# COEXPIX_schematics.net
KiCad netlist of a schematic drawn in Altium Designer
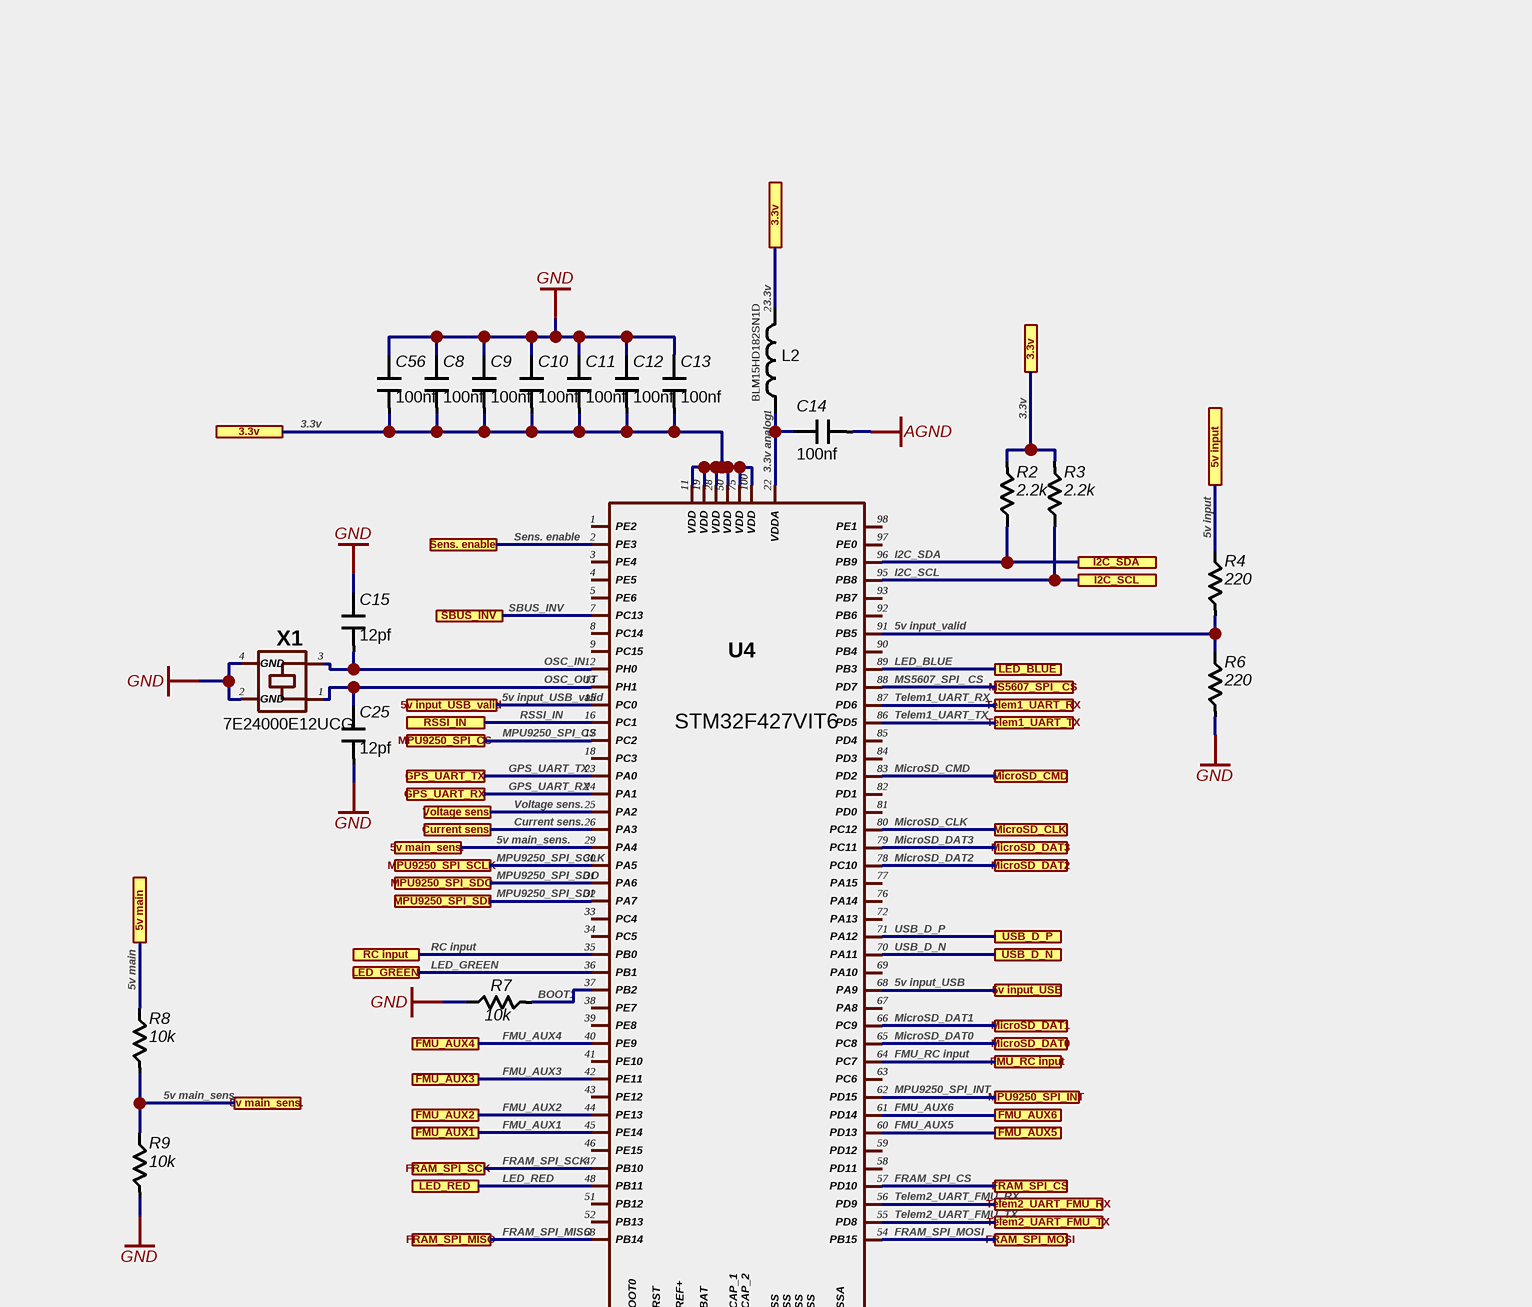
[diagram p0: COEXPIX schematics.SchDoc, top left]
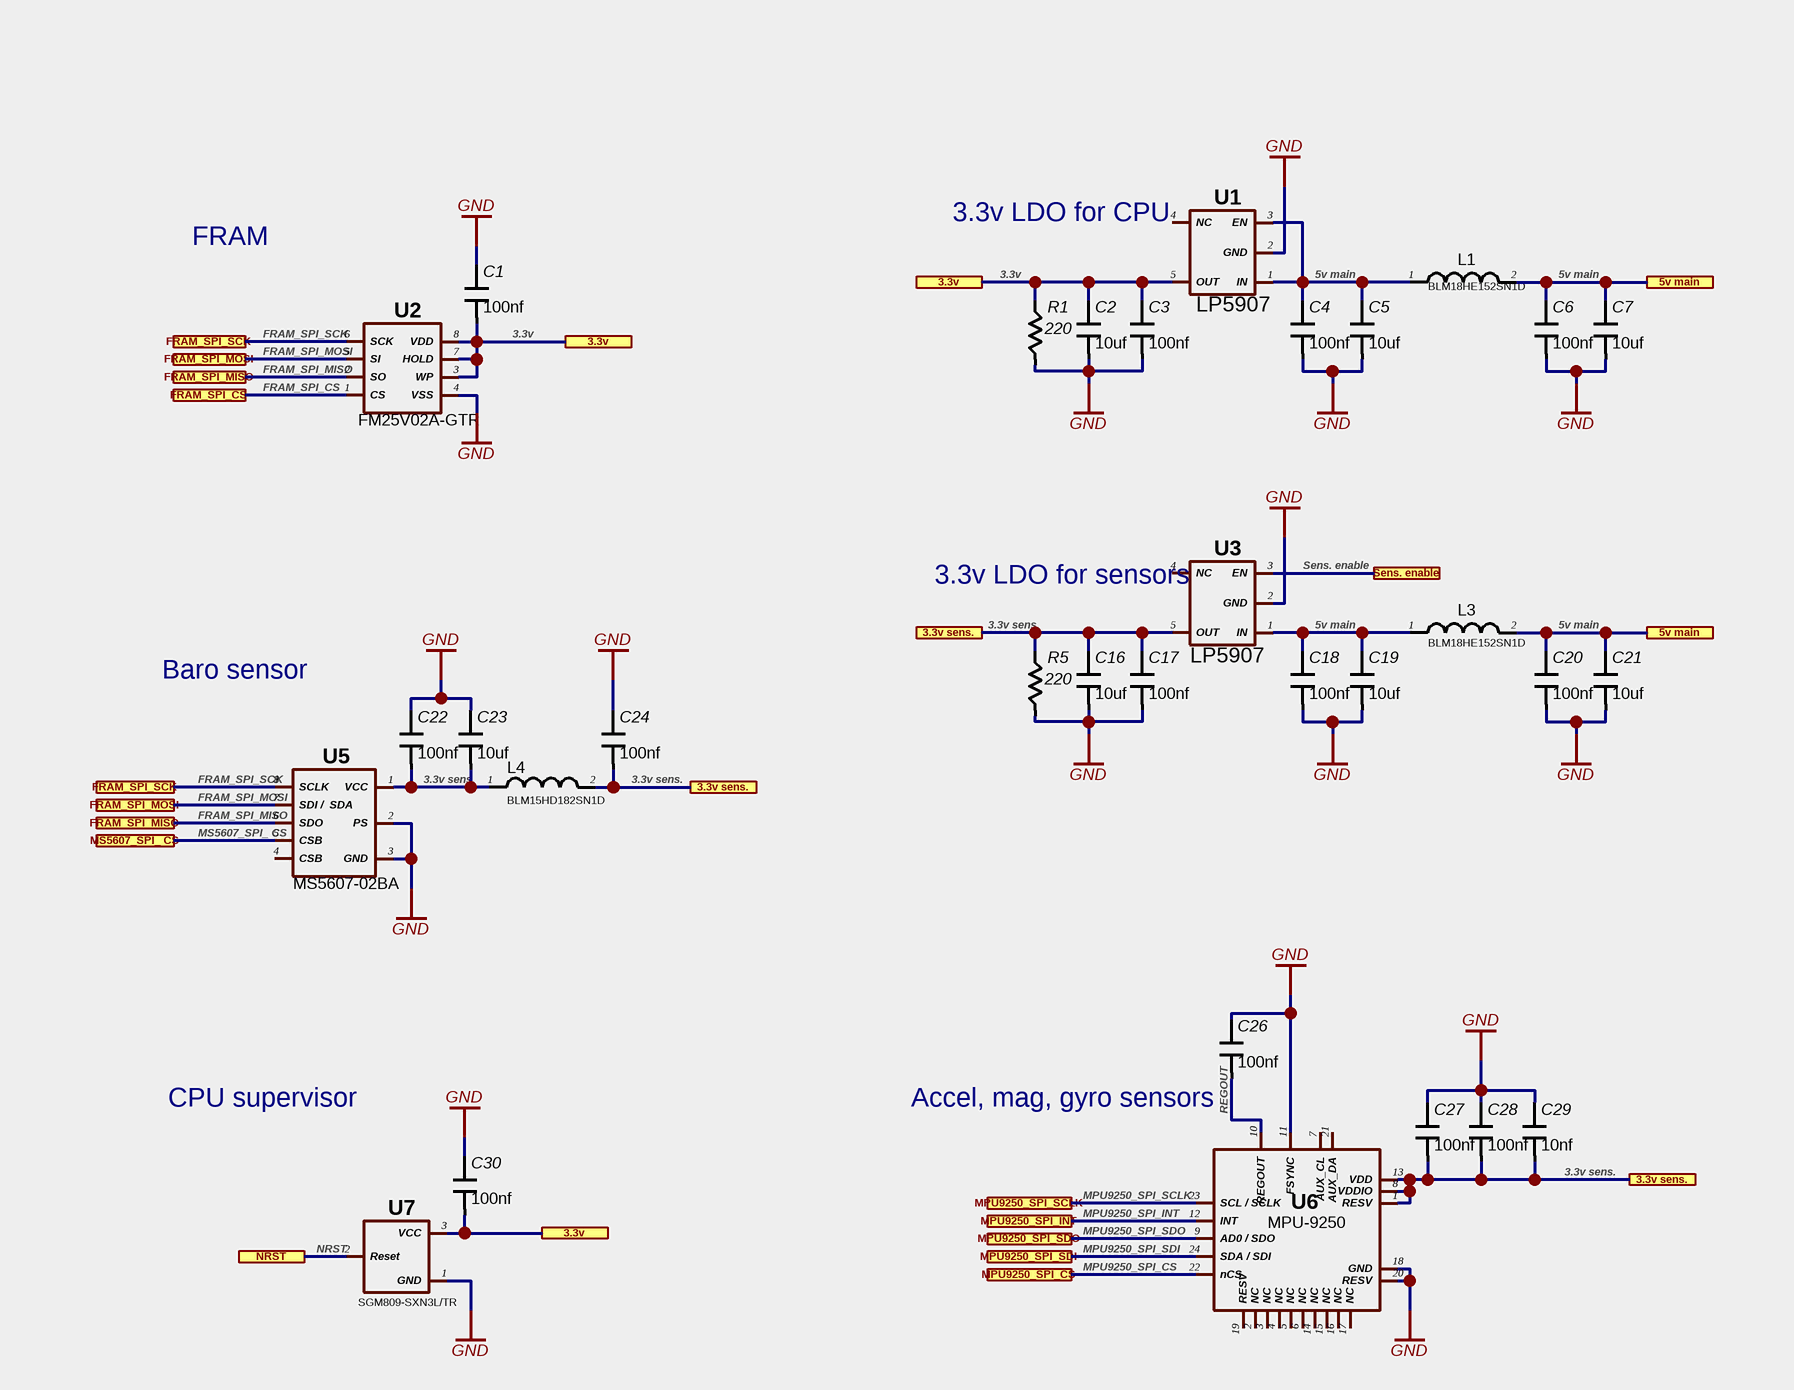
[diagram p1: COEXPIX schematics.SchDoc, top right]
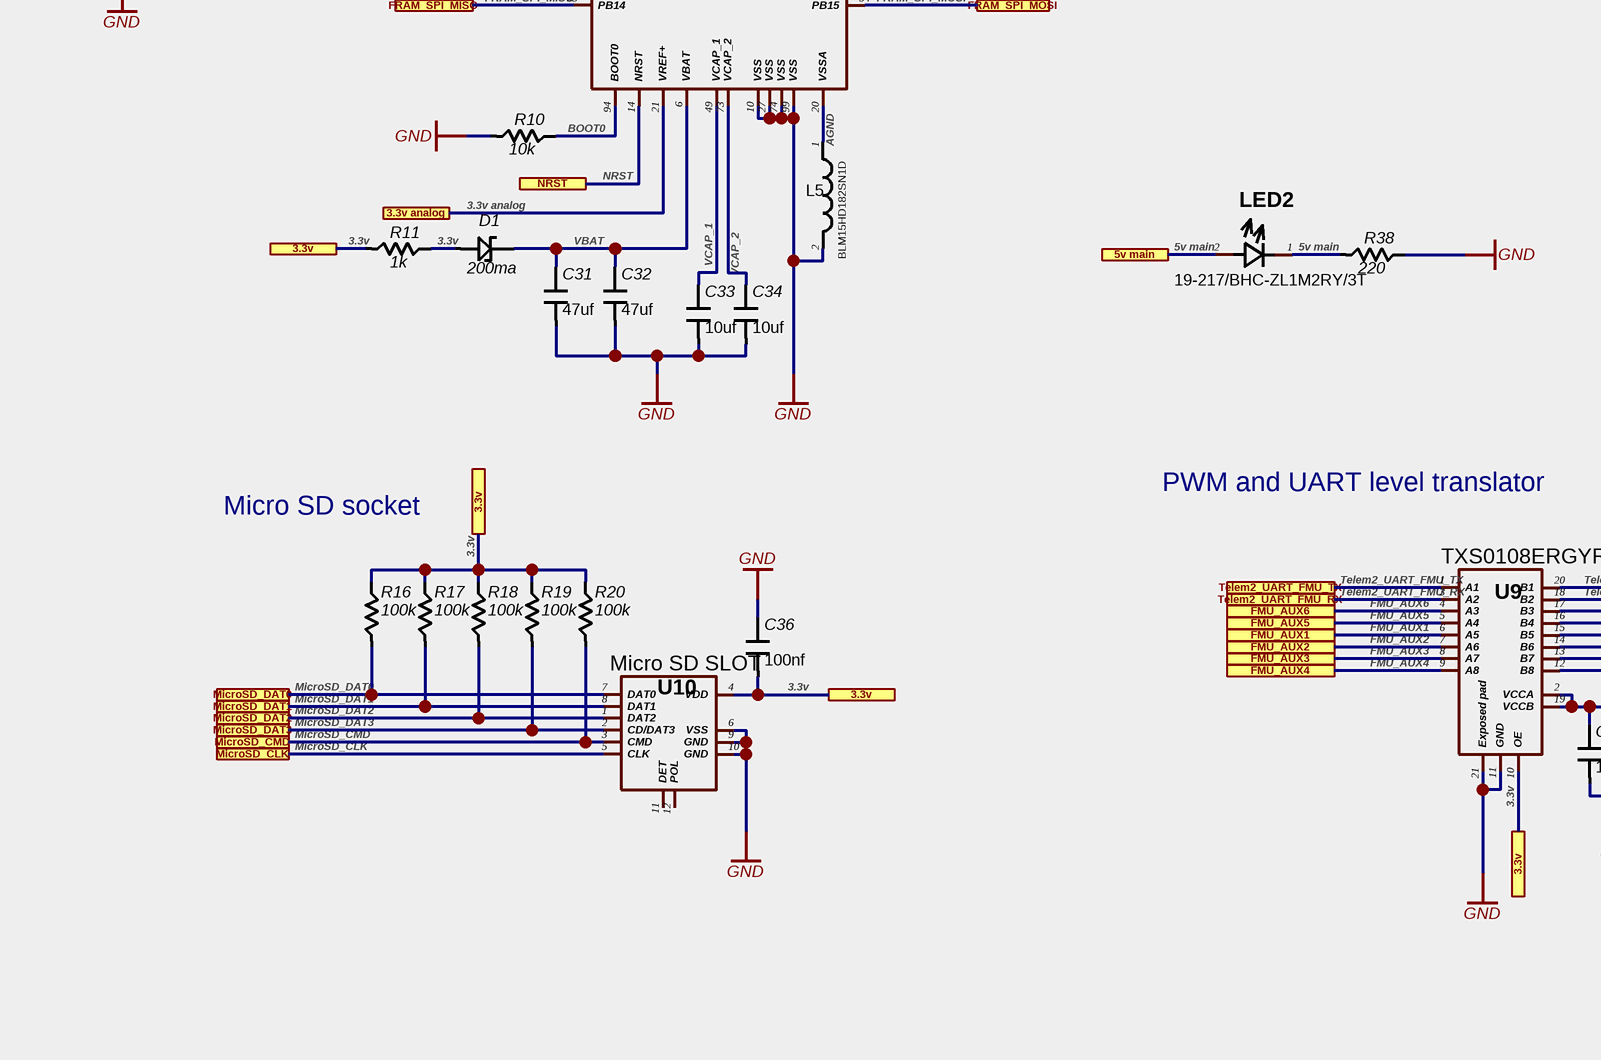
[diagram p2: COEXPIX schematics.SchDoc, bottom left]
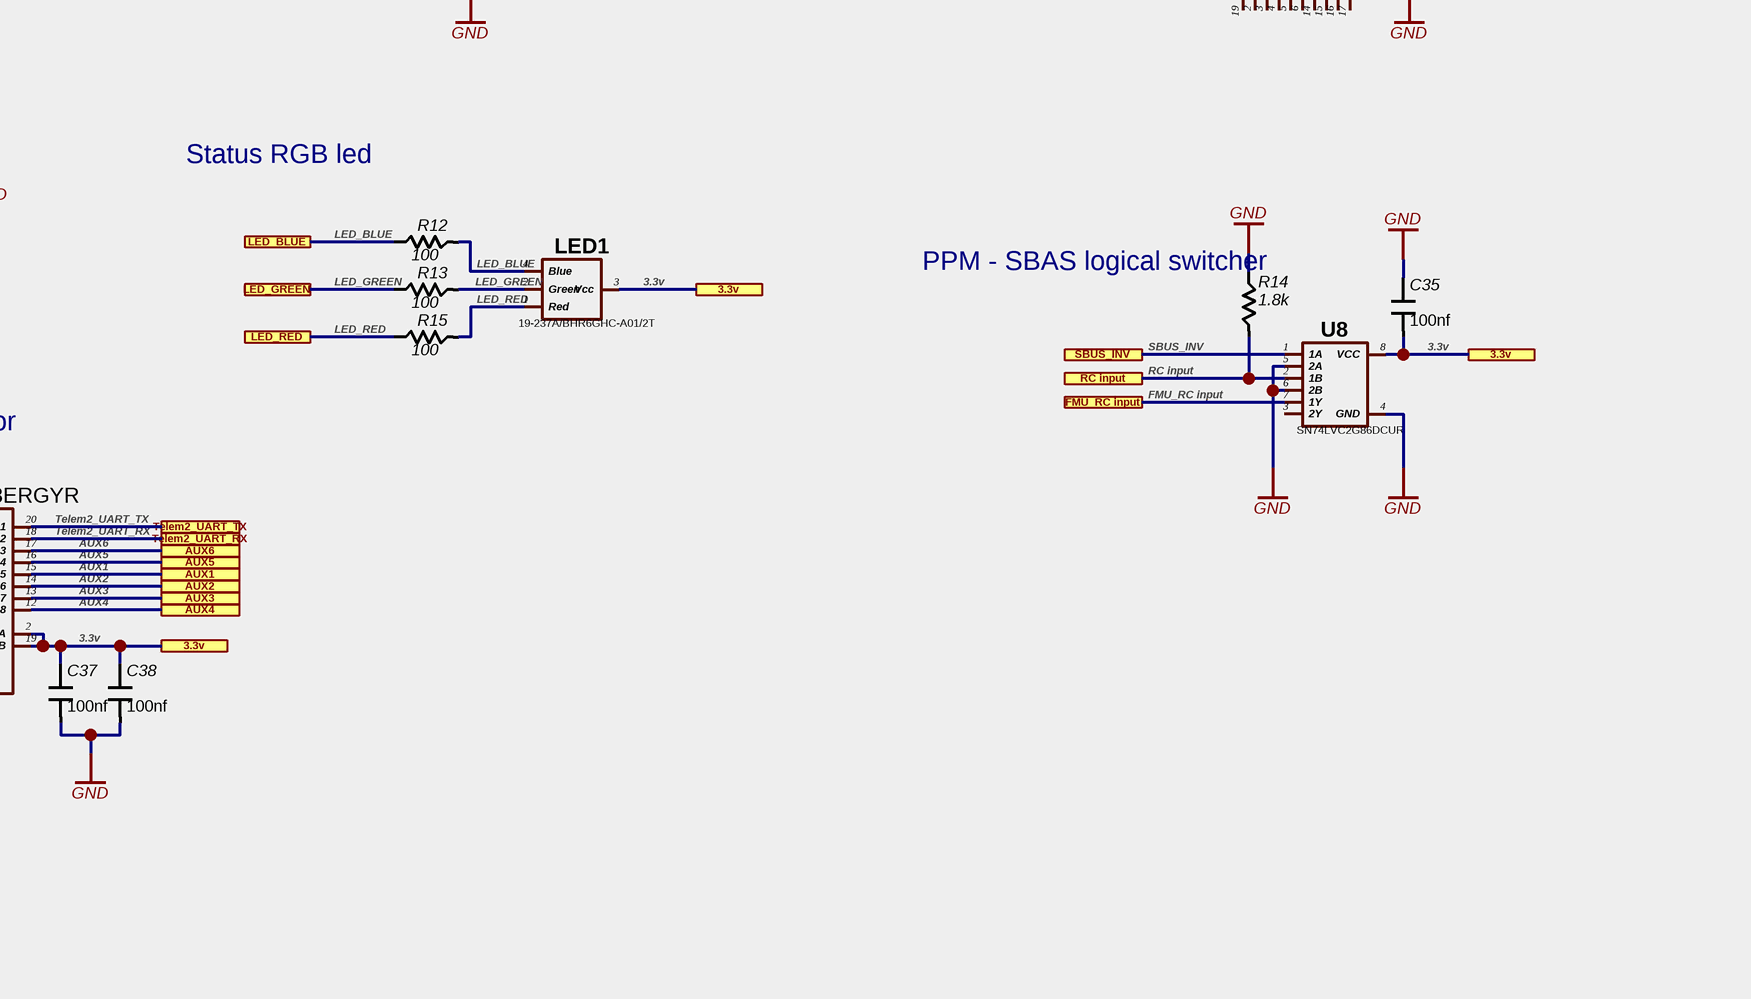
[diagram p3: COEXPIX schematics.SchDoc, bottom right]

(export (version "E")
  (design (tool "Eeschema 10.0.6"))
  (components
    (comp (ref "C1")
      (value "100nf")
      (footprint "Capasitor 0402")
      (description "Multilayer Ceramic Capacitors MLCC - SMD/SMT 100nF 16V 0402")
      (fields (field (name "PART NUMBER") "CC0402KRX7R7BB104") (field (name "MANUFACTURER") "YAGEO"))
      (libsource (lib "Schematic symbols library") (part "Capacitor MLCC"))
    )
    (comp (ref "C2")
      (value "10uf")
      (footprint "Capasitor 0402")
      (description "Multilayer Ceramic Capacitors MLCC - SMD/SMT 10uF 6.3V 0402")
      (fields (field (name "PART NUMBER") "JMK105CBJ106MV-F") (field (name "MANUFACTURER") "Taiyo Yuden"))
      (libsource (lib "Schematic symbols library") (part "Capacitor MLCC"))
    )
    (comp (ref "C3")
      (value "100nf")
      (footprint "Capasitor 0402")
      (description "Multilayer Ceramic Capacitors MLCC - SMD/SMT 100nF 16V 0402")
      (fields (field (name "PART NUMBER") "CC0402KRX7R7BB104") (field (name "MANUFACTURER") "YAGEO"))
      (libsource (lib "Schematic symbols library") (part "Capacitor MLCC"))
    )
    (comp (ref "C4")
      (value "100nf")
      (footprint "Capasitor 0402")
      (description "Multilayer Ceramic Capacitors MLCC - SMD/SMT 100nF 16V 0402")
      (fields (field (name "PART NUMBER") "CC0402KRX7R7BB104") (field (name "MANUFACTURER") "YAGEO"))
      (libsource (lib "Schematic symbols library") (part "Capacitor MLCC"))
    )
    (comp (ref "C5")
      (value "10uf")
      (footprint "Capasitor 0402")
      (description "Multilayer Ceramic Capacitors MLCC - SMD/SMT 10uF 6.3V 0402")
      (fields (field (name "PART NUMBER") "JMK105CBJ106MV-F") (field (name "MANUFACTURER") "Taiyo Yuden"))
      (libsource (lib "") (part "Capacitor MLCC_1"))
    )
    (comp (ref "C6")
      (value "100nf")
      (footprint "Capasitor 0402")
      (description "Multilayer Ceramic Capacitors MLCC - SMD/SMT 100nF 16V 0402")
      (fields (field (name "PART NUMBER") "CC0402KRX7R7BB104") (field (name "MANUFACTURER") "YAGEO"))
      (libsource (lib "Schematic symbols library") (part "Capacitor MLCC"))
    )
    (comp (ref "C7")
      (value "10uf")
      (footprint "Capasitor 0402")
      (description "X5R 6.3v 10uf")
      (fields (field (name "PART NUMBER") "JMK105CBJ106MV-F") (field (name "MANUFACTURER") "Taiyo Yuden"))
      (libsource (lib "Schematic symbols library") (part "Capacitor MLCC"))
    )
    (comp (ref "C8")
      (value "100nf")
      (footprint "Capasitor 0402")
      (description "Multilayer Ceramic Capacitors MLCC - SMD/SMT 100nF 16V 0402")
      (fields (field (name "PART NUMBER") "CC0402KRX7R7BB104") (field (name "MANUFACTURER") "YAGEO"))
      (libsource (lib "Schematic symbols library") (part "Capacitor MLCC"))
    )
    (comp (ref "C9")
      (value "100nf")
      (footprint "Capasitor 0402")
      (description "Multilayer Ceramic Capacitors MLCC - SMD/SMT 100nF 16V 0402")
      (fields (field (name "PART NUMBER") "CC0402KRX7R7BB104") (field (name "MANUFACTURER") "YAGEO"))
      (libsource (lib "Schematic symbols library") (part "Capacitor MLCC"))
    )
    (comp (ref "C10")
      (value "100nf")
      (footprint "Capasitor 0402")
      (description "Multilayer Ceramic Capacitors MLCC - SMD/SMT 100nF 16V 0402")
      (fields (field (name "PART NUMBER") "CC0402KRX7R7BB104") (field (name "MANUFACTURER") "YAGEO"))
      (libsource (lib "Schematic symbols library") (part "Capacitor MLCC"))
    )
    (comp (ref "C11")
      (value "100nf")
      (footprint "Capasitor 0402")
      (description "Multilayer Ceramic Capacitors MLCC - SMD/SMT 100nF 16V 0402")
      (fields (field (name "PART NUMBER") "CC0402KRX7R7BB104") (field (name "MANUFACTURER") "YAGEO"))
      (libsource (lib "Schematic symbols library") (part "Capacitor MLCC"))
    )
    (comp (ref "C12")
      (value "100nf")
      (footprint "Capasitor 0402")
      (description "Multilayer Ceramic Capacitors MLCC - SMD/SMT 100nF 16V 0402")
      (fields (field (name "PART NUMBER") "CC0402KRX7R7BB104") (field (name "MANUFACTURER") "YAGEO"))
      (libsource (lib "Schematic symbols library") (part "Capacitor MLCC"))
    )
    (comp (ref "C13")
      (value "100nf")
      (footprint "Capasitor 0402")
      (description "Multilayer Ceramic Capacitors MLCC - SMD/SMT 100nF 16V 0402")
      (fields (field (name "PART NUMBER") "CC0402KRX7R7BB104") (field (name "MANUFACTURER") "YAGEO"))
      (libsource (lib "Schematic symbols library") (part "Capacitor MLCC"))
    )
    (comp (ref "C14")
      (value "100nf")
      (footprint "Capasitor 0402")
      (description "Multilayer Ceramic Capacitors MLCC - SMD/SMT 100nF 16V 0402")
      (fields (field (name "PART NUMBER") "CC0402KRX7R7BB104") (field (name "MANUFACTURER") "YAGEO"))
      (libsource (lib "Schematic symbols library") (part "Capacitor MLCC"))
    )
    (comp (ref "C15")
      (value "12pf")
      (footprint "Capasitor 0402")
      (description "Multilayer Ceramic Capacitors MLCC - SMD/SMT 12pF 50V 0402")
      (fields (field (name "PART NUMBER") "CC0402JRNPO9BN120") (field (name "MANUFACTURER") "YAGEO"))
      (libsource (lib "Schematic symbols library") (part "Capacitor MLCC"))
    )
    (comp (ref "C16")
      (value "10uf")
      (footprint "Capasitor 0402")
      (description "Multilayer Ceramic Capacitors MLCC - SMD/SMT 10uF 6.3V 0402")
      (fields (field (name "PART NUMBER") "JMK105CBJ106MV-F") (field (name "MANUFACTURER") "Taiyo Yuden"))
      (libsource (lib "Schematic symbols library") (part "Capacitor MLCC"))
    )
    (comp (ref "C17")
      (value "100nf")
      (footprint "Capasitor 0402")
      (description "Multilayer Ceramic Capacitors MLCC - SMD/SMT 100nF 16V 0402")
      (fields (field (name "PART NUMBER") "CC0402KRX7R7BB104") (field (name "MANUFACTURER") "YAGEO"))
      (libsource (lib "Schematic symbols library") (part "Capacitor MLCC"))
    )
    (comp (ref "C18")
      (value "100nf")
      (footprint "Capasitor 0402")
      (description "Multilayer Ceramic Capacitors MLCC - SMD/SMT 100nF 16V 0402")
      (fields (field (name "PART NUMBER") "CC0402KRX7R7BB104") (field (name "MANUFACTURER") "YAGEO"))
      (libsource (lib "Schematic symbols library") (part "Capacitor MLCC"))
    )
    (comp (ref "C19")
      (value "10uf")
      (footprint "Capasitor 0402")
      (description "Multilayer Ceramic Capacitors MLCC - SMD/SMT 10uF 6.3V 0402")
      (fields (field (name "PART NUMBER") "JMK105CBJ106MV-F") (field (name "MANUFACTURER") "Taiyo Yuden"))
      (libsource (lib "") (part "Capacitor MLCC_1"))
    )
    (comp (ref "C20")
      (value "100nf")
      (footprint "Capasitor 0402")
      (description "Multilayer Ceramic Capacitors MLCC - SMD/SMT 100nF 16V 0402")
      (fields (field (name "PART NUMBER") "CC0402KRX7R7BB104") (field (name "MANUFACTURER") "YAGEO"))
      (libsource (lib "Schematic symbols library") (part "Capacitor MLCC"))
    )
    (comp (ref "C21")
      (value "10uf")
      (footprint "Capasitor 0402")
      (description "X5R 6.3v 10uf")
      (fields (field (name "PART NUMBER") "JMK105CBJ106MV-F") (field (name "MANUFACTURER") "Taiyo Yuden"))
      (libsource (lib "Schematic symbols library") (part "Capacitor MLCC"))
    )
    (comp (ref "C22")
      (value "100nf")
      (footprint "Capasitor 0402")
      (description "Multilayer Ceramic Capacitors MLCC - SMD/SMT 100nF 16V 0402")
      (fields (field (name "PART NUMBER") "CC0402KRX7R7BB104") (field (name "MANUFACTURER") "YAGEO"))
      (libsource (lib "Schematic symbols library") (part "Capacitor MLCC"))
    )
    (comp (ref "C23")
      (value "10uf")
      (footprint "Capasitor 0402")
      (description "X5R 6.3v 10uf")
      (fields (field (name "PART NUMBER") "JMK105CBJ106MV-F") (field (name "MANUFACTURER") "Taiyo Yuden"))
      (libsource (lib "Schematic symbols library") (part "Capacitor MLCC"))
    )
    (comp (ref "C24")
      (value "100nf")
      (footprint "Capasitor 0402")
      (description "Multilayer Ceramic Capacitors MLCC - SMD/SMT 100nF 16V 0402")
      (fields (field (name "PART NUMBER") "CC0402KRX7R7BB104") (field (name "MANUFACTURER") "YAGEO"))
      (libsource (lib "Schematic symbols library") (part "Capacitor MLCC"))
    )
    (comp (ref "C25")
      (value "12pf")
      (footprint "Capasitor 0402")
      (description "Multilayer Ceramic Capacitors MLCC - SMD/SMT 12pF 50V 0402")
      (fields (field (name "PART NUMBER") "CC0402JRNPO9BN120") (field (name "MANUFACTURER") "YAGEO"))
      (libsource (lib "Schematic symbols library") (part "Capacitor MLCC"))
    )
    (comp (ref "C26")
      (value "100nf")
      (footprint "Capasitor 0402")
      (description "Multilayer Ceramic Capacitors MLCC - SMD/SMT 100nF 16V 0402")
      (fields (field (name "PART NUMBER") "CC0402KRX7R7BB104") (field (name "MANUFACTURER") "YAGEO"))
      (libsource (lib "Schematic symbols library") (part "Capacitor MLCC"))
    )
    (comp (ref "C27")
      (value "100nf")
      (footprint "Capasitor 0402")
      (description "Multilayer Ceramic Capacitors MLCC - SMD/SMT 100nF 16V 0402")
      (fields (field (name "PART NUMBER") "CC0402KRX7R7BB104") (field (name "MANUFACTURER") "YAGEO"))
      (libsource (lib "Schematic symbols library") (part "Capacitor MLCC"))
    )
    (comp (ref "C28")
      (value "100nf")
      (footprint "Capasitor 0402")
      (description "Multilayer Ceramic Capacitors MLCC - SMD/SMT 100nF 16V 0402")
      (fields (field (name "PART NUMBER") "CC0402KRX7R7BB104") (field (name "MANUFACTURER") "YAGEO"))
      (libsource (lib "Schematic symbols library") (part "Capacitor MLCC"))
    )
    (comp (ref "C29")
      (value "10nf")
      (footprint "Capasitor 0402")
      (description "Multilayer Ceramic Capacitors MLCC - SMD/SMT 10nF 50V 0402")
      (fields (field (name "PART NUMBER") "CC0402KRX7R9BB103") (field (name "MANUFACTURER") "YAGEO"))
      (libsource (lib "Schematic symbols library") (part "Capacitor MLCC"))
    )
    (comp (ref "C30")
      (value "100nf")
      (footprint "Capasitor 0402")
      (description "Multilayer Ceramic Capacitors MLCC - SMD/SMT 100nF 16V 0402")
      (fields (field (name "PART NUMBER") "CC0402KRX7R7BB104") (field (name "MANUFACTURER") "YAGEO"))
      (libsource (lib "Schematic symbols library") (part "Capacitor MLCC"))
    )
    (comp (ref "C31")
      (value "47uf")
      (footprint "Capasitor 0603")
      (description "Multilayer Ceramic Capacitors MLCC - SMD/SMT 47uF 6.3V 0603")
      (fields (field (name "PART NUMBER") "GRM188R60J476ME15D") (field (name "MANUFACTURER") "Murata"))
      (libsource (lib "Schematic symbols library") (part "Capacitor MLCC"))
    )
    (comp (ref "C32")
      (value "47uf")
      (footprint "Capasitor 0603")
      (description "Multilayer Ceramic Capacitors MLCC - SMD/SMT 47uF 6.3V 0603")
      (fields (field (name "PART NUMBER") "GRM188R60J476ME15D") (field (name "MANUFACTURER") "Murata"))
      (libsource (lib "Schematic symbols library") (part "Capacitor MLCC"))
    )
    (comp (ref "C33")
      (value "10uf")
      (footprint "Capasitor 0402")
      (description "Multilayer Ceramic Capacitors MLCC - SMD/SMT 10uF 6.3V 0402")
      (fields (field (name "PART NUMBER") "JMK105CBJ106MV-F") (field (name "MANUFACTURER") "Taiyo Yuden"))
      (libsource (lib "Schematic symbols library") (part "Capacitor MLCC"))
    )
    (comp (ref "C34")
      (value "10uf")
      (footprint "Capasitor 0402")
      (description "Multilayer Ceramic Capacitors MLCC - SMD/SMT 10uF 6.3V 0402")
      (fields (field (name "PART NUMBER") "JMK105CBJ106MV-F") (field (name "MANUFACTURER") "Taiyo Yuden"))
      (libsource (lib "Schematic symbols library") (part "Capacitor MLCC"))
    )
    (comp (ref "C35")
      (value "100nf")
      (footprint "Capasitor 0402")
      (description "Multilayer Ceramic Capacitors MLCC - SMD/SMT 100nF 16V 0402")
      (fields (field (name "PART NUMBER") "CC0402KRX7R7BB104") (field (name "MANUFACTURER") "YAGEO"))
      (libsource (lib "Schematic symbols library") (part "Capacitor MLCC"))
    )
    (comp (ref "C36")
      (value "100nf")
      (footprint "Capasitor 0402")
      (description "Multilayer Ceramic Capacitors MLCC - SMD/SMT 100nF 16V 0402")
      (fields (field (name "PART NUMBER") "CC0402KRX7R7BB104") (field (name "MANUFACTURER") "YAGEO"))
      (libsource (lib "Schematic symbols library") (part "Capacitor MLCC"))
    )
    (comp (ref "C37")
      (value "100nf")
      (footprint "Capasitor 0402")
      (description "Multilayer Ceramic Capacitors MLCC - SMD/SMT 100nF 16V 0402")
      (fields (field (name "PART NUMBER") "CC0402KRX7R7BB104") (field (name "MANUFACTURER") "YAGEO"))
      (libsource (lib "Schematic symbols library") (part "Capacitor MLCC"))
    )
    (comp (ref "C38")
      (value "100nf")
      (footprint "Capasitor 0402")
      (description "Multilayer Ceramic Capacitors MLCC - SMD/SMT 100nF 16V 0402")
      (fields (field (name "PART NUMBER") "CC0402KRX7R7BB104") (field (name "MANUFACTURER") "YAGEO"))
      (libsource (lib "Schematic symbols library") (part "Capacitor MLCC"))
    )
    (comp (ref "C56")
      (value "100nf")
      (footprint "Capasitor 0402")
      (description "Multilayer Ceramic Capacitors MLCC - SMD/SMT 100nF 16V 0402")
      (fields (field (name "PART NUMBER") "CC0402KRX7R7BB104") (field (name "MANUFACTURER") "YAGEO"))
      (libsource (lib "Schematic symbols library") (part "Capacitor MLCC"))
    )
    (comp (ref "D1")
      (value "200ma")
      (footprint "SOD-523F")
      (description "Schottky Barrier Diodes (SBD) SOD-523")
      (fields (field (name "PART NUMBER") "RB521S-30") (field (name "MANUFACTURER") "Shikues"))
      (libsource (lib "Schematic symbols library") (part "Schottky barrier diode"))
    )
    (comp (ref "L1")
      (value "BLM18HE152SN1D")
      (footprint "Ferrite bead 0603")
      (description "Beads 0603")
      (fields (field (name "MANUFACTURER") "Murata"))
      (libsource (lib "Schematic symbols library") (part "FB / Inductor"))
    )
    (comp (ref "L2")
      (value "BLM15HD182SN1D")
      (footprint "Ferrite bead 0402")
      (description "Beads 0402")
      (fields (field (name "MANUFACTURER") "Murata Electronics"))
      (libsource (lib "Schematic symbols library") (part "FB / Inductor"))
    )
    (comp (ref "L3")
      (value "BLM18HE152SN1D")
      (footprint "Ferrite bead 0603")
      (description "Beads 0603")
      (fields (field (name "MANUFACTURER") "Murata"))
      (libsource (lib "Schematic symbols library") (part "FB / Inductor"))
    )
    (comp (ref "L4")
      (value "BLM15HD182SN1D")
      (footprint "Ferrite bead 0402")
      (description "Beads 0402")
      (fields (field (name "MANUFACTURER") "Murata Electronics"))
      (libsource (lib "Schematic symbols library") (part "FB / Inductor"))
    )
    (comp (ref "L5")
      (value "BLM15HD182SN1D")
      (footprint "Ferrite bead 0402")
      (description "Beads 0402")
      (fields (field (name "MANUFACTURER") "Murata Electronics"))
      (libsource (lib "Schematic symbols library") (part "FB / Inductor"))
    )
    (comp (ref "LED1")
      (value "19-237A/BHR6GHC-A01/2T")
      (footprint "Everlight RGB LED")
      (description "RGB LED")
      (fields (field (name "MANUFACTURER") "Everlight"))
      (libsource (lib "Schematic symbols library") (part "Everlight 19-237A"))
    )
    (comp (ref "LED2")
      (value "19-217/BHC-ZL1M2RY/3T")
      (footprint "Led 0603")
      (description "Light Emitting Diodes (LED) Blue 465~475nm 11.5~28.5mcd@5mA Top View 0603")
      (fields (field (name "MANUFACTURER") "Everlight Elec"))
      (libsource (lib "Schematic symbols library") (part "LED"))
    )
    (comp (ref "R1")
      (value "220")
      (footprint "Resistor 0603")
      (description "Chip Resistor - Surface Mount 220Ohms ±1% 1/10W 0603")
      (fields (field (name "PART NUMBER") "0603WAF2200T5E") (field (name "MANUFACTURER") "Uniroyal Elec"))
      (libsource (lib "Schematic symbols library") (part "Resistor"))
    )
    (comp (ref "R2")
      (value "2.2k")
      (footprint "Resistor 0402")
      (description "Chip Resistor - Surface Mount 2.2KOhms ±1% 1/16W 0402")
      (fields (field (name "PART NUMBER") "RC0402FR-072K2L") (field (name "MANUFACTURER") "YAGEO"))
      (libsource (lib "Schematic symbols library") (part "Resistor"))
    )
    (comp (ref "R3")
      (value "2.2k")
      (footprint "Resistor 0402")
      (description "Chip Resistor - Surface Mount 2.2KOhms ±1% 1/16W 0402")
      (fields (field (name "PART NUMBER") "RC0402FR-072K2L") (field (name "MANUFACTURER") "YAGEO"))
      (libsource (lib "Schematic symbols library") (part "Resistor"))
    )
    (comp (ref "R4")
      (value "220")
      (footprint "Resistor 0402")
      (description "Chip Resistor - Surface Mount 220Ohms ±1% 1/16W 0402")
      (fields (field (name "PART NUMBER") "0402WGF2200TCE") (field (name "MANUFACTURER") "Uniroyal Elec"))
      (libsource (lib "Schematic symbols library") (part "Resistor"))
    )
    (comp (ref "R5")
      (value "220")
      (footprint "Resistor 0603")
      (description "Chip Resistor - Surface Mount 220Ohms ±1% 1/10W 0603")
      (fields (field (name "PART NUMBER") "0603WAF2200T5E") (field (name "MANUFACTURER") "Uniroyal Elec"))
      (libsource (lib "Schematic symbols library") (part "Resistor"))
    )
    (comp (ref "R6")
      (value "220")
      (footprint "Resistor 0402")
      (description "Chip Resistor - Surface Mount 220Ohms ±1% 1/16W 0402")
      (fields (field (name "PART NUMBER") "0402WGF2200TCE") (field (name "MANUFACTURER") "Uniroyal Elec"))
      (libsource (lib "Schematic symbols library") (part "Resistor"))
    )
    (comp (ref "R7")
      (value "10k")
      (footprint "Resistor 0402")
      (description "Chip Resistor - Surface Mount 10KOhms ±1% 1/16W 0402")
      (fields (field (name "PART NUMBER") "RC0402FR-0710KL") (field (name "MANUFACTURER") "YAGEO"))
      (libsource (lib "Schematic symbols library") (part "Resistor"))
    )
    (comp (ref "R8")
      (value "10k")
      (footprint "Resistor 0402")
      (description "Chip Resistor - Surface Mount 10KOhms ±1% 1/16W 0402")
      (fields (field (name "PART NUMBER") "RC0402FR-0710KL") (field (name "MANUFACTURER") "YAGEO"))
      (libsource (lib "Schematic symbols library") (part "Resistor"))
    )
    (comp (ref "R9")
      (value "10k")
      (footprint "Resistor 0402")
      (description "Chip Resistor - Surface Mount 10KOhms ±1% 1/16W 0402")
      (fields (field (name "PART NUMBER") "RC0402FR-0710KL") (field (name "MANUFACTURER") "YAGEO"))
      (libsource (lib "Schematic symbols library") (part "Resistor"))
    )
    (comp (ref "R10")
      (value "10k")
      (footprint "Resistor 0402")
      (description "Chip Resistor - Surface Mount 10KOhms ±1% 1/16W 0402")
      (fields (field (name "PART NUMBER") "RC0402FR-0710KL") (field (name "MANUFACTURER") "YAGEO"))
      (libsource (lib "Schematic symbols library") (part "Resistor"))
    )
    (comp (ref "R11")
      (value "1k")
      (footprint "Resistor 0402")
      (description "Chip Resistor - Surface Mount 1KOhms ±1% 1/16W 0402")
      (fields (field (name "PART NUMBER") "RC0402FR-071KL") (field (name "MANUFACTURER") "YAGEO"))
      (libsource (lib "Schematic symbols library") (part "Resistor"))
    )
    (comp (ref "R12")
      (value "100")
      (footprint "Resistor 0402")
      (description "Chip Resistor - Surface Mount 100Ohms ±1% 1/16W 0402")
      (fields (field (name "PART NUMBER") "RC0402FR-07100RL") (field (name "MANUFACTURER") "YAGEO"))
      (libsource (lib "Schematic symbols library") (part "Resistor"))
    )
    (comp (ref "R13")
      (value "100")
      (footprint "Resistor 0402")
      (description "Chip Resistor - Surface Mount 100Ohms ±1% 1/16W 0402")
      (fields (field (name "PART NUMBER") "RC0402FR-07100RL") (field (name "MANUFACTURER") "YAGEO"))
      (libsource (lib "Schematic symbols library") (part "Resistor"))
    )
    (comp (ref "R14")
      (value "1.8k")
      (footprint "Resistor 0402")
      (description "Chip Resistor - Surface Mount 1.8KOhms ±1% 1/16W 0402")
      (fields (field (name "PART NUMBER") "0402WGF1801TCE") (field (name "MANUFACTURER") "Uniroyal Elec"))
      (libsource (lib "Schematic symbols library") (part "Resistor"))
    )
    (comp (ref "R15")
      (value "100")
      (footprint "Resistor 0402")
      (description "Chip Resistor - Surface Mount 100Ohms ±1% 1/16W 0402")
      (fields (field (name "PART NUMBER") "RC0402FR-07100RL") (field (name "MANUFACTURER") "YAGEO"))
      (libsource (lib "Schematic symbols library") (part "Resistor"))
    )
    (comp (ref "R16")
      (value "100k")
      (footprint "Resistor 0402")
      (description "Chip Resistor - Surface Mount 100KOhms ±1% 1/16W 0402")
      (fields (field (name "PART NUMBER") "RC0402FR-07100KL") (field (name "MANUFACTURER") "YAGEO"))
      (libsource (lib "Schematic symbols library") (part "Resistor"))
    )
    (comp (ref "R17")
      (value "100k")
      (footprint "Resistor 0402")
      (description "Chip Resistor - Surface Mount 100KOhms ±1% 1/16W 0402")
      (fields (field (name "PART NUMBER") "RC0402FR-07100KL") (field (name "MANUFACTURER") "YAGEO"))
      (libsource (lib "Schematic symbols library") (part "Resistor"))
    )
    (comp (ref "R18")
      (value "100k")
      (footprint "Resistor 0402")
      (description "Chip Resistor - Surface Mount 100KOhms ±1% 1/16W 0402")
      (fields (field (name "PART NUMBER") "RC0402FR-07100KL") (field (name "MANUFACTURER") "YAGEO"))
      (libsource (lib "Schematic symbols library") (part "Resistor"))
    )
    (comp (ref "R19")
      (value "100k")
      (footprint "Resistor 0402")
      (description "Chip Resistor - Surface Mount 100KOhms ±1% 1/16W 0402")
      (fields (field (name "PART NUMBER") "RC0402FR-07100KL") (field (name "MANUFACTURER") "YAGEO"))
      (libsource (lib "Schematic symbols library") (part "Resistor"))
    )
    (comp (ref "R20")
      (value "100k")
      (footprint "Resistor 0402")
      (description "Chip Resistor - Surface Mount 100KOhms ±1% 1/16W 0402")
      (fields (field (name "PART NUMBER") "RC0402FR-07100KL") (field (name "MANUFACTURER") "YAGEO"))
      (libsource (lib "Schematic symbols library") (part "Resistor"))
    )
    (comp (ref "R38")
      (value "220")
      (footprint "Resistor 0402")
      (description "Chip Resistor - Surface Mount 220Ohms ±1% 1/16W 0402")
      (fields (field (name "PART NUMBER") "0402WGF2200TCE") (field (name "MANUFACTURER") "Uniroyal Elec"))
      (libsource (lib "Schematic symbols library") (part "Resistor"))
    )
    (comp (ref "U1")
      (value "LP5907")
      (footprint "SOT23-5")
      (description "Linear Voltage Regulators SOT-23-5")
      (fields (field (name "MANUFACTURER") "Texas Instruments"))
      (libsource (lib "Schematic symbols library") (part "LP5907"))
    )
    (comp (ref "U2")
      (value "FM25V02A-GTR")
      (footprint "SOIC-8")
      (description "FRAM FRAM 256Kb (32K x 8) SPI SOIC-8_150mil")
      (fields (field (name "MANUFACTURER") "Cypress Semicon"))
      (libsource (lib "Schematic symbols library") (part "FM25V02A"))
    )
    (comp (ref "U3")
      (value "LP5907")
      (footprint "SOT23-5")
      (description "Linear Voltage Regulators SOT-23-5")
      (fields (field (name "MANUFACTURER") "Texas Instruments"))
      (libsource (lib "Schematic symbols library") (part "LP5907"))
    )
    (comp (ref "U4")
      (value "STM32F427VIT6")
      (footprint "LQFP100")
      (description "ARM® Cortex®-M4 STM32F4 Microcontroller IC 32-Bit 180MHz 2MB (2M x 8) FLASH 100-LQFP (14x14)")
      (fields (field (name "MANUFACTURER") "STMicroelectronics"))
      (libsource (lib "Schematic symbols library") (part "STM32F427VIT6"))
    )
    (comp (ref "U5")
      (value "MS5607-02BA")
      (footprint "MS5611")
      (fields (field (name "MANUFACTURER") "meas-spec"))
      (libsource (lib "Schematic symbols library") (part "MS5607-02BA"))
    )
    (comp (ref "U6")
      (value "MPU-9250")
      (footprint "mpu9250")
      (description "IMU ACCEL/GYRO/MAG I2C/SPI 24QFN")
      (fields (field (name "MANUFACTURER") "TDK InvenSense"))
      (libsource (lib "Schematic symbols library") (part "mpu9250"))
    )
    (comp (ref "U7")
      (value "SGM809-SXN3L/TR")
      (footprint "SOT23-3 LP")
      (fields (field (name "MANUFACTURER") "SGMICRO"))
      (libsource (lib "Schematic symbols library") (part "SGM809-SXN3L/TR"))
    )
    (comp (ref "U8")
      (value "SN74LVC2G86DCUR")
      (footprint "VSSOP8 0.5mm")
      (description "74 Series SPST-NC 2 1.65V ~ 5.5V VSSOP-8_2x2.3x05P")
      (fields (field (name "MANUFACTURER") "Texas Instruments"))
      (libsource (lib "Schematic symbols library") (part "SN74LVC2G86DCUR"))
    )
    (comp (ref "U9")
      (value "TXS0108ERGYR")
      (footprint "VQFN20 4.50x3.50mm (0.5mm)")
      (description "Level Translators, Shifters VQFN-20")
      (fields (field (name "MANUFACTURER") "Texas Instruments"))
      (libsource (lib "Schematic symbols library") (part "TXS0108ERGYR"))
    )
    (comp (ref "U10")
      (value "Micro SD SLOT")
      (footprint "Micro SD slot")
      (libsource (lib "Schematic symbols library") (part "MicroSD socket"))
    )
    (comp (ref "X1")
      (value "7E24000E12UCG")
      (footprint "SMD-2520_4P")
      (description "SMD Crystal Resonators 24MHz ±10ppm SMD-2520_4P")
      (fields (field (name "MANUFACTURER") "SHENZHEN CRYSTAL TECH"))
      (libsource (lib "Schematic symbols library") (part "Crystal oscillator"))
    )
  )
  (nets
    (net (code "1") (name "/3.3v") (class "Default")
      (node (ref "C1") (pin "2") (pinfunction "2_2") (pintype "passive"))
      (node (ref "C10") (pin "2") (pinfunction "2_2") (pintype "passive"))
      (node (ref "C11") (pin "2") (pinfunction "2_2") (pintype "passive"))
      (node (ref "C12") (pin "2") (pinfunction "2_2") (pintype "passive"))
      (node (ref "C13") (pin "2") (pinfunction "2_2") (pintype "passive"))
      (node (ref "C2") (pin "1") (pinfunction "1_1") (pintype "passive"))
      (node (ref "C3") (pin "1") (pinfunction "1_1") (pintype "passive"))
      (node (ref "C30") (pin "2") (pinfunction "2_2") (pintype "passive"))
      (node (ref "C35") (pin "2") (pinfunction "2_2") (pintype "passive"))
      (node (ref "C36") (pin "2") (pinfunction "2_2") (pintype "passive"))
      (node (ref "C37") (pin "1") (pinfunction "1_1") (pintype "passive"))
      (node (ref "C38") (pin "1") (pinfunction "1_1") (pintype "passive"))
      (node (ref "C56") (pin "2") (pinfunction "2_2") (pintype "passive"))
      (node (ref "C8") (pin "2") (pinfunction "2_2") (pintype "passive"))
      (node (ref "C9") (pin "2") (pinfunction "2_2") (pintype "passive"))
      (node (ref "D1") (pin "2") (pinfunction "2_2") (pintype "passive"))
      (node (ref "L2") (pin "2") (pintype "power_in"))
      (node (ref "LED1") (pin "3") (pinfunction "Vcc_3") (pintype "power_in"))
      (node (ref "R1") (pin "1") (pinfunction "1_1") (pintype "passive"))
      (node (ref "R11") (pin "1") (pinfunction "1_1") (pintype "passive"))
      (node (ref "R11") (pin "2") (pinfunction "2_2") (pintype "passive"))
      (node (ref "R16") (pin "1") (pinfunction "1_1") (pintype "passive"))
      (node (ref "R17") (pin "1") (pinfunction "1_1") (pintype "passive"))
      (node (ref "R18") (pin "1") (pinfunction "1_1") (pintype "passive"))
      (node (ref "R19") (pin "1") (pinfunction "1_1") (pintype "passive"))
      (node (ref "R2") (pin "2") (pinfunction "2_2") (pintype "passive"))
      (node (ref "R20") (pin "1") (pinfunction "1_1") (pintype "passive"))
      (node (ref "R3") (pin "2") (pinfunction "2_2") (pintype "passive"))
      (node (ref "U1") (pin "5") (pinfunction "OUT_5") (pintype "power_in"))
      (node (ref "U10") (pin "4") (pinfunction "VDD_4") (pintype "power_in"))
      (node (ref "U2") (pin "3") (pinfunction "WP_3") (pintype "power_in"))
      (node (ref "U2") (pin "7") (pinfunction "HOLD_7") (pintype "power_in"))
      (node (ref "U2") (pin "8") (pinfunction "VDD_8") (pintype "power_in"))
      (node (ref "U4") (pin "100") (pinfunction "VDD_100") (pintype "power_in"))
      (node (ref "U4") (pin "11") (pinfunction "VDD_11") (pintype "power_in"))
      (node (ref "U4") (pin "19") (pinfunction "VDD_19") (pintype "power_in"))
      (node (ref "U4") (pin "28") (pinfunction "VDD_28") (pintype "power_in"))
      (node (ref "U4") (pin "50") (pinfunction "VDD_50") (pintype "power_in"))
      (node (ref "U4") (pin "75") (pinfunction "VDD_75") (pintype "power_in"))
      (node (ref "U7") (pin "3") (pinfunction "VCC_3") (pintype "power_in"))
      (node (ref "U8") (pin "8") (pinfunction "VCC_8") (pintype "power_in"))
      (node (ref "U9") (pin "10") (pinfunction "OE_10") (pintype "power_in"))
      (node (ref "U9") (pin "19") (pinfunction "VCCB_19") (pintype "power_in"))
      (node (ref "U9") (pin "2") (pinfunction "VCCA_2") (pintype "power_in"))
    )
    (net (code "2") (name "/3.3v analog") (class "Default")
      (node (ref "C14") (pin "1") (pinfunction "1_1") (pintype "passive"))
      (node (ref "L2") (pin "1") (pintype "power_in"))
      (node (ref "U4") (pin "21") (pinfunction "VREF+_21") (pintype "power_in"))
      (node (ref "U4") (pin "22") (pinfunction "VDDA_22") (pintype "power_in"))
    )
    (net (code "3") (name "/3.3v sens.") (class "Default")
      (node (ref "C16") (pin "1") (pinfunction "1_1") (pintype "passive"))
      (node (ref "C17") (pin "1") (pinfunction "1_1") (pintype "passive"))
      (node (ref "C22") (pin "2") (pinfunction "2_2") (pintype "passive"))
      (node (ref "C23") (pin "2") (pinfunction "2_2") (pintype "passive"))
      (node (ref "C24") (pin "2") (pinfunction "2_2") (pintype "passive"))
      (node (ref "C27") (pin "2") (pinfunction "2_2") (pintype "passive"))
      (node (ref "C28") (pin "2") (pinfunction "2_2") (pintype "passive"))
      (node (ref "C29") (pin "2") (pinfunction "2_2") (pintype "passive"))
      (node (ref "L4") (pin "1") (pintype "power_in"))
      (node (ref "L4") (pin "2") (pintype "power_in"))
      (node (ref "R5") (pin "1") (pinfunction "1_1") (pintype "passive"))
      (node (ref "U3") (pin "5") (pinfunction "OUT_5") (pintype "power_in"))
      (node (ref "U5") (pin "1") (pinfunction "VCC_1") (pintype "power_in"))
      (node (ref "U6") (pin "1") (pinfunction "RESV_1") (pintype "power_in"))
      (node (ref "U6") (pin "13") (pinfunction "VDD_13") (pintype "power_in"))
      (node (ref "U6") (pin "8") (pinfunction "VDDIO_8") (pintype "power_in"))
    )
    (net (code "4") (name "/5v input") (class "Default")
      (node (ref "R4") (pin "1") (pinfunction "1_1") (pintype "passive"))
    )
    (net (code "5") (name "/5v input_USB") (class "Default")
      (node (ref "U4") (pin "68") (pinfunction "PA9_68") (pintype "power_in"))
    )
    (net (code "6") (name "/5v input_USB_valid") (class "Default")
      (node (ref "U4") (pin "15") (pinfunction "PC0_15") (pintype "power_in"))
    )
    (net (code "7") (name "/5v input_valid") (class "Default")
      (node (ref "R4") (pin "2") (pinfunction "2_2") (pintype "passive"))
      (node (ref "R6") (pin "1") (pinfunction "1_1") (pintype "passive"))
      (node (ref "U4") (pin "91") (pinfunction "PB5_91") (pintype "power_in"))
    )
    (net (code "8") (name "/5v main") (class "Default")
      (node (ref "C18") (pin "1") (pinfunction "1_1") (pintype "passive"))
      (node (ref "C19") (pin "1") (pinfunction "1_1") (pintype "passive"))
      (node (ref "C20") (pin "1") (pinfunction "1_1") (pintype "passive"))
      (node (ref "C21") (pin "1") (pinfunction "1_1") (pintype "passive"))
      (node (ref "C4") (pin "1") (pinfunction "1_1") (pintype "passive"))
      (node (ref "C5") (pin "1") (pinfunction "1_1") (pintype "passive"))
      (node (ref "C6") (pin "1") (pinfunction "1_1") (pintype "passive"))
      (node (ref "C7") (pin "1") (pinfunction "1_1") (pintype "passive"))
      (node (ref "L1") (pin "1") (pintype "power_in"))
      (node (ref "L1") (pin "2") (pintype "power_in"))
      (node (ref "L3") (pin "1") (pintype "power_in"))
      (node (ref "L3") (pin "2") (pintype "power_in"))
      (node (ref "LED2") (pin "1") (pintype "power_in"))
      (node (ref "LED2") (pin "2") (pintype "power_in"))
      (node (ref "R38") (pin "2") (pinfunction "2_2") (pintype "passive"))
      (node (ref "R8") (pin "1") (pinfunction "1_1") (pintype "passive"))
      (node (ref "U1") (pin "1") (pinfunction "IN_1") (pintype "power_in"))
      (node (ref "U1") (pin "3") (pinfunction "EN_3") (pintype "power_in"))
      (node (ref "U3") (pin "1") (pinfunction "IN_1") (pintype "power_in"))
    )
    (net (code "9") (name "/5v main_sens.") (class "Default")
      (node (ref "R8") (pin "2") (pinfunction "2_2") (pintype "passive"))
      (node (ref "R9") (pin "1") (pinfunction "1_1") (pintype "passive"))
      (node (ref "U4") (pin "29") (pinfunction "PA4_29") (pintype "power_in"))
    )
    (net (code "10") (name "/AUX1") (class "Default")
      (node (ref "U9") (pin "15") (pinfunction "B5_15") (pintype "power_in"))
    )
    (net (code "11") (name "/AUX2") (class "Default")
      (node (ref "U9") (pin "14") (pinfunction "B6_14") (pintype "power_in"))
    )
    (net (code "12") (name "/AUX3") (class "Default")
      (node (ref "U9") (pin "13") (pinfunction "B7_13") (pintype "power_in"))
    )
    (net (code "13") (name "/AUX4") (class "Default")
      (node (ref "U9") (pin "12") (pinfunction "B8_12") (pintype "power_in"))
    )
    (net (code "14") (name "/AUX5") (class "Default")
      (node (ref "U9") (pin "16") (pinfunction "B4_16") (pintype "power_in"))
    )
    (net (code "15") (name "/AUX6") (class "Default")
      (node (ref "U9") (pin "17") (pinfunction "B3_17") (pintype "power_in"))
    )
    (net (code "16") (name "/BOOT0") (class "Default")
      (node (ref "R10") (pin "1") (pinfunction "1_1") (pintype "passive"))
      (node (ref "U4") (pin "94") (pinfunction "BOOT0_94") (pintype "power_in"))
    )
    (net (code "17") (name "/BOOT1") (class "Default")
      (node (ref "R7") (pin "2") (pinfunction "2_2") (pintype "passive"))
      (node (ref "U4") (pin "37") (pinfunction "PB2_37") (pintype "power_in"))
    )
    (net (code "18") (name "/Current sens.") (class "Default")
      (node (ref "U4") (pin "26") (pinfunction "PA3_26") (pintype "power_in"))
    )
    (net (code "19") (name "/FMU_AUX1") (class "Default")
      (node (ref "U4") (pin "45") (pinfunction "PE14_45") (pintype "power_in"))
      (node (ref "U9") (pin "6") (pinfunction "A5_6") (pintype "power_in"))
    )
    (net (code "20") (name "/FMU_AUX2") (class "Default")
      (node (ref "U4") (pin "44") (pinfunction "PE13_44") (pintype "power_in"))
      (node (ref "U9") (pin "7") (pinfunction "A6_7") (pintype "power_in"))
    )
    (net (code "21") (name "/FMU_AUX3") (class "Default")
      (node (ref "U4") (pin "42") (pinfunction "PE11_42") (pintype "power_in"))
      (node (ref "U9") (pin "8") (pinfunction "A7_8") (pintype "power_in"))
    )
    (net (code "22") (name "/FMU_AUX4") (class "Default")
      (node (ref "U4") (pin "40") (pinfunction "PE9_40") (pintype "power_in"))
      (node (ref "U9") (pin "9") (pinfunction "A8_9") (pintype "power_in"))
    )
    (net (code "23") (name "/FMU_AUX5") (class "Default")
      (node (ref "U4") (pin "60") (pinfunction "PD13_60") (pintype "power_in"))
      (node (ref "U9") (pin "5") (pinfunction "A4_5") (pintype "power_in"))
    )
    (net (code "24") (name "/FMU_AUX6") (class "Default")
      (node (ref "U4") (pin "61") (pinfunction "PD14_61") (pintype "power_in"))
      (node (ref "U9") (pin "4") (pinfunction "A3_4") (pintype "power_in"))
    )
    (net (code "25") (name "/FMU_RC input") (class "Default")
      (node (ref "U4") (pin "64") (pinfunction "PC7_64") (pintype "power_in"))
      (node (ref "U8") (pin "7") (pinfunction "1Y_7") (pintype "power_in"))
    )
    (net (code "26") (name "/FRAM_SPI_CS") (class "Default")
      (node (ref "U2") (pin "1") (pinfunction "CS_1") (pintype "power_in"))
      (node (ref "U4") (pin "57") (pinfunction "PD10_57") (pintype "power_in"))
    )
    (net (code "27") (name "/FRAM_SPI_MISO") (class "Default")
      (node (ref "U2") (pin "2") (pinfunction "SO_2") (pintype "power_in"))
      (node (ref "U4") (pin "53") (pinfunction "PB14_53") (pintype "power_in"))
      (node (ref "U5") (pin "6") (pinfunction "SDO_6") (pintype "power_in"))
    )
    (net (code "28") (name "/FRAM_SPI_MOSI") (class "Default")
      (node (ref "U2") (pin "5") (pinfunction "SI_5") (pintype "power_in"))
      (node (ref "U4") (pin "54") (pinfunction "PB15_54") (pintype "power_in"))
      (node (ref "U5") (pin "7") (pinfunction "SDI_/__SDA_7") (pintype "power_in"))
    )
    (net (code "29") (name "/FRAM_SPI_SCK") (class "Default")
      (node (ref "U2") (pin "6") (pinfunction "SCK_6") (pintype "power_in"))
      (node (ref "U4") (pin "47") (pinfunction "PB10_47") (pintype "power_in"))
      (node (ref "U5") (pin "8") (pinfunction "SCLK_8") (pintype "power_in"))
    )
    (net (code "30") (name "/GPS_UART_RX") (class "Default")
      (node (ref "U4") (pin "24") (pinfunction "PA1_24") (pintype "power_in"))
    )
    (net (code "31") (name "/GPS_UART_TX") (class "Default")
      (node (ref "U4") (pin "23") (pinfunction "PA0_23") (pintype "power_in"))
    )
    (net (code "32") (name "/I2C_SCL") (class "Default")
      (node (ref "R3") (pin "1") (pinfunction "1_1") (pintype "passive"))
      (node (ref "U4") (pin "95") (pinfunction "PB8_95") (pintype "power_in"))
    )
    (net (code "33") (name "/I2C_SDA") (class "Default")
      (node (ref "R2") (pin "1") (pinfunction "1_1") (pintype "passive"))
      (node (ref "U4") (pin "96") (pinfunction "PB9_96") (pintype "power_in"))
    )
    (net (code "34") (name "/LED_BLUE") (class "Default")
      (node (ref "LED1") (pin "4") (pinfunction "Blue_4") (pintype "power_in"))
      (node (ref "R12") (pin "1") (pinfunction "1_1") (pintype "passive"))
      (node (ref "R12") (pin "2") (pinfunction "2_2") (pintype "passive"))
      (node (ref "U4") (pin "89") (pinfunction "PB3_89") (pintype "power_in"))
    )
    (net (code "35") (name "/LED_GREEN") (class "Default")
      (node (ref "LED1") (pin "2") (pinfunction "Green_2") (pintype "power_in"))
      (node (ref "R13") (pin "1") (pinfunction "1_1") (pintype "passive"))
      (node (ref "R13") (pin "2") (pinfunction "2_2") (pintype "passive"))
      (node (ref "U4") (pin "36") (pinfunction "PB1_36") (pintype "power_in"))
    )
    (net (code "36") (name "/LED_RED") (class "Default")
      (node (ref "LED1") (pin "1") (pinfunction "Red_1") (pintype "power_in"))
      (node (ref "R15") (pin "1") (pinfunction "1_1") (pintype "passive"))
      (node (ref "R15") (pin "2") (pinfunction "2_2") (pintype "passive"))
      (node (ref "U4") (pin "48") (pinfunction "PB11_48") (pintype "power_in"))
    )
    (net (code "37") (name "/MPU9250_SPI_CS") (class "Default")
      (node (ref "U4") (pin "17") (pinfunction "PC2_17") (pintype "power_in"))
      (node (ref "U6") (pin "22") (pinfunction "nCS_22") (pintype "power_in"))
    )
    (net (code "38") (name "/MPU9250_SPI_INT") (class "Default")
      (node (ref "U4") (pin "62") (pinfunction "PD15_62") (pintype "power_in"))
      (node (ref "U6") (pin "12") (pinfunction "INT_12") (pintype "power_in"))
    )
    (net (code "39") (name "/MPU9250_SPI_SCLK") (class "Default")
      (node (ref "U4") (pin "30") (pinfunction "PA5_30") (pintype "power_in"))
      (node (ref "U6") (pin "23") (pinfunction "SCL_/_SCLK_23") (pintype "power_in"))
    )
    (net (code "40") (name "/MPU9250_SPI_SDI") (class "Default")
      (node (ref "U4") (pin "32") (pinfunction "PA7_32") (pintype "power_in"))
      (node (ref "U6") (pin "24") (pinfunction "SDA_/_SDI_24") (pintype "power_in"))
    )
    (net (code "41") (name "/MPU9250_SPI_SDO") (class "Default")
      (node (ref "U4") (pin "31") (pinfunction "PA6_31") (pintype "power_in"))
      (node (ref "U6") (pin "9") (pinfunction "AD0_/_SDO_9") (pintype "power_in"))
    )
    (net (code "42") (name "/MS5607_SPI_ CS") (class "Default")
      (node (ref "U4") (pin "88") (pinfunction "PD7_88") (pintype "power_in"))
      (node (ref "U5") (pin "5") (pinfunction "CSB_5") (pintype "power_in"))
    )
    (net (code "43") (name "/MicroSD_CLK") (class "Default")
      (node (ref "U10") (pin "5") (pinfunction "CLK_5") (pintype "power_in"))
      (node (ref "U4") (pin "80") (pinfunction "PC12_80") (pintype "power_in"))
    )
    (net (code "44") (name "/MicroSD_CMD") (class "Default")
      (node (ref "R20") (pin "2") (pinfunction "2_2") (pintype "passive"))
      (node (ref "U10") (pin "3") (pinfunction "CMD_3") (pintype "power_in"))
      (node (ref "U4") (pin "83") (pinfunction "PD2_83") (pintype "power_in"))
    )
    (net (code "45") (name "/MicroSD_DAT0") (class "Default")
      (node (ref "R16") (pin "2") (pinfunction "2_2") (pintype "passive"))
      (node (ref "U10") (pin "7") (pinfunction "DAT0_7") (pintype "power_in"))
      (node (ref "U4") (pin "65") (pinfunction "PC8_65") (pintype "power_in"))
    )
    (net (code "46") (name "/MicroSD_DAT1") (class "Default")
      (node (ref "R17") (pin "2") (pinfunction "2_2") (pintype "passive"))
      (node (ref "U10") (pin "8") (pinfunction "DAT1_8") (pintype "power_in"))
      (node (ref "U4") (pin "66") (pinfunction "PC9_66") (pintype "power_in"))
    )
    (net (code "47") (name "/MicroSD_DAT2") (class "Default")
      (node (ref "R18") (pin "2") (pinfunction "2_2") (pintype "passive"))
      (node (ref "U10") (pin "1") (pinfunction "DAT2_1") (pintype "power_in"))
      (node (ref "U4") (pin "78") (pinfunction "PC10_78") (pintype "power_in"))
    )
    (net (code "48") (name "/MicroSD_DAT3") (class "Default")
      (node (ref "R19") (pin "2") (pinfunction "2_2") (pintype "passive"))
      (node (ref "U10") (pin "2") (pinfunction "CD/DAT3_2") (pintype "power_in"))
      (node (ref "U4") (pin "79") (pinfunction "PC11_79") (pintype "power_in"))
    )
    (net (code "49") (name "/NRST") (class "Default")
      (node (ref "U4") (pin "14") (pinfunction "NRST_14") (pintype "power_in"))
      (node (ref "U7") (pin "2") (pinfunction "Reset_2") (pintype "power_in"))
    )
    (net (code "50") (name "/OSC_IN") (class "Default")
      (node (ref "C15") (pin "2") (pinfunction "2_2") (pintype "passive"))
      (node (ref "U4") (pin "12") (pinfunction "PH0_12") (pintype "power_in"))
      (node (ref "X1") (pin "3") (pintype "power_in"))
    )
    (net (code "51") (name "/OSC_OUT") (class "Default")
      (node (ref "C25") (pin "1") (pinfunction "1_1") (pintype "passive"))
      (node (ref "U4") (pin "13") (pinfunction "PH1_13") (pintype "power_in"))
      (node (ref "X1") (pin "1") (pintype "power_in"))
    )
    (net (code "52") (name "/RC input") (class "Default")
      (node (ref "R14") (pin "2") (pinfunction "2_2") (pintype "passive"))
      (node (ref "U4") (pin "35") (pinfunction "PB0_35") (pintype "power_in"))
      (node (ref "U8") (pin "2") (pinfunction "1B_2") (pintype "power_in"))
    )
    (net (code "53") (name "/REGOUT") (class "Default")
      (node (ref "C26") (pin "2") (pinfunction "2_2") (pintype "passive"))
      (node (ref "U6") (pin "10") (pinfunction "REGOUT_10") (pintype "power_in"))
    )
    (net (code "54") (name "/RSSI_IN") (class "Default")
      (node (ref "U4") (pin "16") (pinfunction "PC1_16") (pintype "power_in"))
    )
    (net (code "55") (name "/SBUS_INV") (class "Default")
      (node (ref "U4") (pin "7") (pinfunction "PC13_7") (pintype "power_in"))
      (node (ref "U8") (pin "1") (pinfunction "1A_1") (pintype "power_in"))
    )
    (net (code "56") (name "/Sens. enable") (class "Default")
      (node (ref "U3") (pin "3") (pinfunction "EN_3") (pintype "power_in"))
      (node (ref "U4") (pin "2") (pinfunction "PE3_2") (pintype "power_in"))
    )
    (net (code "57") (name "/Telem1_UART_RX") (class "Default")
      (node (ref "U4") (pin "87") (pinfunction "PD6_87") (pintype "power_in"))
    )
    (net (code "58") (name "/Telem1_UART_TX") (class "Default")
      (node (ref "U4") (pin "86") (pinfunction "PD5_86") (pintype "power_in"))
    )
    (net (code "59") (name "/Telem2_UART_FMU_RX") (class "Default")
      (node (ref "U4") (pin "56") (pinfunction "PD9_56") (pintype "power_in"))
      (node (ref "U9") (pin "3") (pinfunction "A2_3") (pintype "power_in"))
    )
    (net (code "60") (name "/Telem2_UART_FMU_TX") (class "Default")
      (node (ref "U4") (pin "55") (pinfunction "PD8_55") (pintype "power_in"))
      (node (ref "U9") (pin "1") (pinfunction "A1_1") (pintype "power_in"))
    )
    (net (code "61") (name "/Telem2_UART_RX") (class "Default")
      (node (ref "U9") (pin "18") (pinfunction "B2_18") (pintype "power_in"))
    )
    (net (code "62") (name "/Telem2_UART_TX") (class "Default")
      (node (ref "U9") (pin "20") (pinfunction "B1_20") (pintype "power_in"))
    )
    (net (code "63") (name "/USB_D_N") (class "Default")
      (node (ref "U4") (pin "70") (pinfunction "PA11_70") (pintype "power_in"))
    )
    (net (code "64") (name "/USB_D_P") (class "Default")
      (node (ref "U4") (pin "71") (pinfunction "PA12_71") (pintype "power_in"))
    )
    (net (code "65") (name "/VBAT") (class "Default")
      (node (ref "C31") (pin "1") (pinfunction "1_1") (pintype "passive"))
      (node (ref "C32") (pin "1") (pinfunction "1_1") (pintype "passive"))
      (node (ref "D1") (pin "1") (pinfunction "1_1") (pintype "passive"))
      (node (ref "U4") (pin "6") (pinfunction "VBAT_6") (pintype "power_in"))
    )
    (net (code "66") (name "/VCAP_1") (class "Default")
      (node (ref "C33") (pin "1") (pinfunction "1_1") (pintype "passive"))
      (node (ref "U4") (pin "49") (pinfunction "VCAP_1_49") (pintype "power_in"))
    )
    (net (code "67") (name "/VCAP_2") (class "Default")
      (node (ref "C34") (pin "1") (pinfunction "1_1") (pintype "passive"))
      (node (ref "U4") (pin "73") (pinfunction "VCAP_2_73") (pintype "power_in"))
    )
    (net (code "68") (name "/Voltage sens.") (class "Default")
      (node (ref "U4") (pin "25") (pinfunction "PA2_25") (pintype "power_in"))
    )
    (net (code "69") (name "AGND") (class "Default")
      (node (ref "C14") (pin "2") (pinfunction "2_2") (pintype "passive"))
      (node (ref "L5") (pin "1") (pintype "power_in"))
      (node (ref "U4") (pin "20") (pinfunction "VSSA_20") (pintype "power_in"))
    )
    (net (code "70") (name "GND") (class "Default")
      (node (ref "C1") (pin "1") (pinfunction "1_1") (pintype "passive"))
      (node (ref "C10") (pin "1") (pinfunction "1_1") (pintype "passive"))
      (node (ref "C11") (pin "1") (pinfunction "1_1") (pintype "passive"))
      (node (ref "C12") (pin "1") (pinfunction "1_1") (pintype "passive"))
      (node (ref "C13") (pin "1") (pinfunction "1_1") (pintype "passive"))
      (node (ref "C15") (pin "1") (pinfunction "1_1") (pintype "passive"))
      (node (ref "C16") (pin "2") (pinfunction "2_2") (pintype "passive"))
      (node (ref "C17") (pin "2") (pinfunction "2_2") (pintype "passive"))
      (node (ref "C18") (pin "2") (pinfunction "2_2") (pintype "passive"))
      (node (ref "C19") (pin "2") (pinfunction "2_2") (pintype "passive"))
      (node (ref "C2") (pin "2") (pinfunction "2_2") (pintype "passive"))
      (node (ref "C20") (pin "2") (pinfunction "2_2") (pintype "passive"))
      (node (ref "C21") (pin "2") (pinfunction "2_2") (pintype "passive"))
      (node (ref "C22") (pin "1") (pinfunction "1_1") (pintype "passive"))
      (node (ref "C23") (pin "1") (pinfunction "1_1") (pintype "passive"))
      (node (ref "C24") (pin "1") (pinfunction "1_1") (pintype "passive"))
      (node (ref "C25") (pin "2") (pinfunction "2_2") (pintype "passive"))
      (node (ref "C26") (pin "1") (pinfunction "1_1") (pintype "passive"))
      (node (ref "C27") (pin "1") (pinfunction "1_1") (pintype "passive"))
      (node (ref "C28") (pin "1") (pinfunction "1_1") (pintype "passive"))
      (node (ref "C29") (pin "1") (pinfunction "1_1") (pintype "passive"))
      (node (ref "C3") (pin "2") (pinfunction "2_2") (pintype "passive"))
      (node (ref "C30") (pin "1") (pinfunction "1_1") (pintype "passive"))
      (node (ref "C31") (pin "2") (pinfunction "2_2") (pintype "passive"))
      (node (ref "C32") (pin "2") (pinfunction "2_2") (pintype "passive"))
      (node (ref "C33") (pin "2") (pinfunction "2_2") (pintype "passive"))
      (node (ref "C34") (pin "2") (pinfunction "2_2") (pintype "passive"))
      (node (ref "C35") (pin "1") (pinfunction "1_1") (pintype "passive"))
      (node (ref "C36") (pin "1") (pinfunction "1_1") (pintype "passive"))
      (node (ref "C37") (pin "2") (pinfunction "2_2") (pintype "passive"))
      (node (ref "C38") (pin "2") (pinfunction "2_2") (pintype "passive"))
      (node (ref "C4") (pin "2") (pinfunction "2_2") (pintype "passive"))
      (node (ref "C5") (pin "2") (pinfunction "2_2") (pintype "passive"))
      (node (ref "C56") (pin "1") (pinfunction "1_1") (pintype "passive"))
      (node (ref "C6") (pin "2") (pinfunction "2_2") (pintype "passive"))
      (node (ref "C7") (pin "2") (pinfunction "2_2") (pintype "passive"))
      (node (ref "C8") (pin "1") (pinfunction "1_1") (pintype "passive"))
      (node (ref "C9") (pin "1") (pinfunction "1_1") (pintype "passive"))
      (node (ref "L5") (pin "2") (pintype "power_in"))
      (node (ref "R1") (pin "2") (pinfunction "2_2") (pintype "passive"))
      (node (ref "R10") (pin "2") (pinfunction "2_2") (pintype "passive"))
      (node (ref "R14") (pin "1") (pinfunction "1_1") (pintype "passive"))
      (node (ref "R38") (pin "1") (pinfunction "1_1") (pintype "passive"))
      (node (ref "R5") (pin "2") (pinfunction "2_2") (pintype "passive"))
      (node (ref "R6") (pin "2") (pinfunction "2_2") (pintype "passive"))
      (node (ref "R7") (pin "1") (pinfunction "1_1") (pintype "passive"))
      (node (ref "R9") (pin "2") (pinfunction "2_2") (pintype "passive"))
      (node (ref "U1") (pin "2") (pinfunction "GND_2") (pintype "power_in"))
      (node (ref "U10") (pin "10") (pinfunction "GND_10") (pintype "power_in"))
      (node (ref "U10") (pin "6") (pinfunction "VSS_6") (pintype "power_in"))
      (node (ref "U10") (pin "9") (pinfunction "GND_9") (pintype "power_in"))
      (node (ref "U2") (pin "4") (pinfunction "VSS_4") (pintype "power_in"))
      (node (ref "U3") (pin "2") (pinfunction "GND_2") (pintype "power_in"))
      (node (ref "U4") (pin "10") (pinfunction "VSS_10") (pintype "power_in"))
      (node (ref "U4") (pin "27") (pinfunction "VSS_27") (pintype "power_in"))
      (node (ref "U4") (pin "74") (pinfunction "VSS_74") (pintype "power_in"))
      (node (ref "U4") (pin "99") (pinfunction "VSS_99") (pintype "power_in"))
      (node (ref "U5") (pin "2") (pinfunction "PS_2") (pintype "power_in"))
      (node (ref "U5") (pin "3") (pinfunction "GND_3") (pintype "power_in"))
      (node (ref "U6") (pin "11") (pinfunction "FSYNC_11") (pintype "power_in"))
      (node (ref "U6") (pin "18") (pinfunction "GND_18") (pintype "power_in"))
      (node (ref "U6") (pin "20") (pinfunction "RESV_20") (pintype "power_in"))
      (node (ref "U7") (pin "1") (pinfunction "GND_1") (pintype "power_in"))
      (node (ref "U8") (pin "4") (pinfunction "GND_4") (pintype "power_in"))
      (node (ref "U8") (pin "5") (pinfunction "2A_5") (pintype "power_in"))
      (node (ref "U8") (pin "6") (pinfunction "2B_6") (pintype "power_in"))
      (node (ref "U9") (pin "11") (pinfunction "GND_11") (pintype "power_in"))
      (node (ref "U9") (pin "21") (pinfunction "Exposed_pad_21") (pintype "power_in"))
      (node (ref "X1") (pin "2") (pinfunction "GND_2") (pintype "power_in"))
      (node (ref "X1") (pin "4") (pinfunction "GND_4") (pintype "power_in"))
    )
    (net (code "71") (name "unconnected-(U1-NC-Pad4)") (class "Default")
      (node (ref "U1") (pin "4") (pinfunction "NC_4") (pintype "open_collector"))
    )
    (net (code "72") (name "unconnected-(U3-NC-Pad4)") (class "Default")
      (node (ref "U3") (pin "4") (pinfunction "NC_4") (pintype "open_collector"))
    )
    (net (code "73") (name "unconnected-(U4-PA8-Pad67)") (class "Default")
      (node (ref "U4") (pin "67") (pinfunction "PA8_67") (pintype "power_in"))
    )
    (net (code "74") (name "unconnected-(U4-PA10-Pad69)") (class "Default")
      (node (ref "U4") (pin "69") (pinfunction "PA10_69") (pintype "power_in"))
    )
    (net (code "75") (name "unconnected-(U4-PA13-Pad72)") (class "Default")
      (node (ref "U4") (pin "72") (pinfunction "PA13_72") (pintype "power_in"))
    )
    (net (code "76") (name "unconnected-(U4-PA14-Pad76)") (class "Default")
      (node (ref "U4") (pin "76") (pinfunction "PA14_76") (pintype "power_in"))
    )
    (net (code "77") (name "unconnected-(U4-PA15-Pad77)") (class "Default")
      (node (ref "U4") (pin "77") (pinfunction "PA15_77") (pintype "power_in"))
    )
    (net (code "78") (name "unconnected-(U4-PB4-Pad90)") (class "Default")
      (node (ref "U4") (pin "90") (pinfunction "PB4_90") (pintype "power_in"))
    )
    (net (code "79") (name "unconnected-(U4-PB6-Pad92)") (class "Default")
      (node (ref "U4") (pin "92") (pinfunction "PB6_92") (pintype "power_in"))
    )
    (net (code "80") (name "unconnected-(U4-PB7-Pad93)") (class "Default")
      (node (ref "U4") (pin "93") (pinfunction "PB7_93") (pintype "power_in"))
    )
    (net (code "81") (name "unconnected-(U4-PB12-Pad51)") (class "Default")
      (node (ref "U4") (pin "51") (pinfunction "PB12_51") (pintype "power_in"))
    )
    (net (code "82") (name "unconnected-(U4-PB13-Pad52)") (class "Default")
      (node (ref "U4") (pin "52") (pinfunction "PB13_52") (pintype "power_in"))
    )
    (net (code "83") (name "unconnected-(U4-PC3-Pad18)") (class "Default")
      (node (ref "U4") (pin "18") (pinfunction "PC3_18") (pintype "power_in"))
    )
    (net (code "84") (name "unconnected-(U4-PC4-Pad33)") (class "Default")
      (node (ref "U4") (pin "33") (pinfunction "PC4_33") (pintype "power_in"))
    )
    (net (code "85") (name "unconnected-(U4-PC5-Pad34)") (class "Default")
      (node (ref "U4") (pin "34") (pinfunction "PC5_34") (pintype "power_in"))
    )
    (net (code "86") (name "unconnected-(U4-PC6-Pad63)") (class "Default")
      (node (ref "U4") (pin "63") (pinfunction "PC6_63") (pintype "power_in"))
    )
    (net (code "87") (name "unconnected-(U4-PC14-Pad8)") (class "Default")
      (node (ref "U4") (pin "8") (pinfunction "PC14_8") (pintype "power_in"))
    )
    (net (code "88") (name "unconnected-(U4-PC15-Pad9)") (class "Default")
      (node (ref "U4") (pin "9") (pinfunction "PC15_9") (pintype "power_in"))
    )
    (net (code "89") (name "unconnected-(U4-PD0-Pad81)") (class "Default")
      (node (ref "U4") (pin "81") (pinfunction "PD0_81") (pintype "power_in"))
    )
    (net (code "90") (name "unconnected-(U4-PD1-Pad82)") (class "Default")
      (node (ref "U4") (pin "82") (pinfunction "PD1_82") (pintype "power_in"))
    )
    (net (code "91") (name "unconnected-(U4-PD3-Pad84)") (class "Default")
      (node (ref "U4") (pin "84") (pinfunction "PD3_84") (pintype "power_in"))
    )
    (net (code "92") (name "unconnected-(U4-PD4-Pad85)") (class "Default")
      (node (ref "U4") (pin "85") (pinfunction "PD4_85") (pintype "power_in"))
    )
    (net (code "93") (name "unconnected-(U4-PD11-Pad58)") (class "Default")
      (node (ref "U4") (pin "58") (pinfunction "PD11_58") (pintype "power_in"))
    )
    (net (code "94") (name "unconnected-(U4-PD12-Pad59)") (class "Default")
      (node (ref "U4") (pin "59") (pinfunction "PD12_59") (pintype "power_in"))
    )
    (net (code "95") (name "unconnected-(U4-PE0-Pad97)") (class "Default")
      (node (ref "U4") (pin "97") (pinfunction "PE0_97") (pintype "power_in"))
    )
    (net (code "96") (name "unconnected-(U4-PE1-Pad98)") (class "Default")
      (node (ref "U4") (pin "98") (pinfunction "PE1_98") (pintype "power_in"))
    )
    (net (code "97") (name "unconnected-(U4-PE2-Pad1)") (class "Default")
      (node (ref "U4") (pin "1") (pinfunction "PE2_1") (pintype "power_in"))
    )
    (net (code "98") (name "unconnected-(U4-PE4-Pad3)") (class "Default")
      (node (ref "U4") (pin "3") (pinfunction "PE4_3") (pintype "power_in"))
    )
    (net (code "99") (name "unconnected-(U4-PE5-Pad4)") (class "Default")
      (node (ref "U4") (pin "4") (pinfunction "PE5_4") (pintype "power_in"))
    )
    (net (code "100") (name "unconnected-(U4-PE6-Pad5)") (class "Default")
      (node (ref "U4") (pin "5") (pinfunction "PE6_5") (pintype "power_in"))
    )
    (net (code "101") (name "unconnected-(U4-PE7-Pad38)") (class "Default")
      (node (ref "U4") (pin "38") (pinfunction "PE7_38") (pintype "power_in"))
    )
    (net (code "102") (name "unconnected-(U4-PE8-Pad39)") (class "Default")
      (node (ref "U4") (pin "39") (pinfunction "PE8_39") (pintype "power_in"))
    )
    (net (code "103") (name "unconnected-(U4-PE10-Pad41)") (class "Default")
      (node (ref "U4") (pin "41") (pinfunction "PE10_41") (pintype "power_in"))
    )
    (net (code "104") (name "unconnected-(U4-PE12-Pad43)") (class "Default")
      (node (ref "U4") (pin "43") (pinfunction "PE12_43") (pintype "power_in"))
    )
    (net (code "105") (name "unconnected-(U4-PE15-Pad46)") (class "Default")
      (node (ref "U4") (pin "46") (pinfunction "PE15_46") (pintype "power_in"))
    )
    (net (code "106") (name "unconnected-(U5-CSB-Pad4)") (class "Default")
      (node (ref "U5") (pin "4") (pinfunction "CSB_4") (pintype "power_in"))
    )
    (net (code "107") (name "unconnected-(U6-AUX_CL-Pad7)") (class "Default")
      (node (ref "U6") (pin "7") (pinfunction "AUX_CL_7") (pintype "power_in"))
    )
    (net (code "108") (name "unconnected-(U6-AUX_DA-Pad21)") (class "Default")
      (node (ref "U6") (pin "21") (pinfunction "AUX_DA_21") (pintype "power_in"))
    )
    (net (code "109") (name "unconnected-(U6-NC-Pad2)") (class "Default")
      (node (ref "U6") (pin "2") (pinfunction "NC_2") (pintype "power_in"))
    )
    (net (code "110") (name "unconnected-(U6-NC-Pad3)") (class "Default")
      (node (ref "U6") (pin "3") (pinfunction "NC_3") (pintype "power_in"))
    )
    (net (code "111") (name "unconnected-(U6-NC-Pad4)") (class "Default")
      (node (ref "U6") (pin "4") (pinfunction "NC_4") (pintype "power_in"))
    )
    (net (code "112") (name "unconnected-(U6-NC-Pad5)") (class "Default")
      (node (ref "U6") (pin "5") (pinfunction "NC_5") (pintype "power_in"))
    )
    (net (code "113") (name "unconnected-(U6-NC-Pad6)") (class "Default")
      (node (ref "U6") (pin "6") (pinfunction "NC_6") (pintype "power_in"))
    )
    (net (code "114") (name "unconnected-(U6-NC-Pad14)") (class "Default")
      (node (ref "U6") (pin "14") (pinfunction "NC_14") (pintype "power_in"))
    )
    (net (code "115") (name "unconnected-(U6-NC-Pad15)") (class "Default")
      (node (ref "U6") (pin "15") (pinfunction "NC_15") (pintype "power_in"))
    )
    (net (code "116") (name "unconnected-(U6-NC-Pad16)") (class "Default")
      (node (ref "U6") (pin "16") (pinfunction "NC_16") (pintype "power_in"))
    )
    (net (code "117") (name "unconnected-(U6-NC-Pad17)") (class "Default")
      (node (ref "U6") (pin "17") (pinfunction "NC_17") (pintype "power_in"))
    )
    (net (code "118") (name "unconnected-(U6-RESV-Pad19)") (class "Default")
      (node (ref "U6") (pin "19") (pinfunction "RESV_19") (pintype "power_in"))
    )
    (net (code "119") (name "unconnected-(U8-2Y-Pad3)") (class "Default")
      (node (ref "U8") (pin "3") (pinfunction "2Y_3") (pintype "power_in"))
    )
    (net (code "120") (name "unconnected-(U10-DET-Pad11)") (class "Default")
      (node (ref "U10") (pin "11") (pinfunction "DET_11") (pintype "power_in"))
    )
    (net (code "121") (name "unconnected-(U10-POL-Pad12)") (class "Default")
      (node (ref "U10") (pin "12") (pinfunction "POL_12") (pintype "power_in"))
    )
  )
)
